# DB25-relay-HV-control.net
KiCad netlist of a schematic drawn in Altium Designer
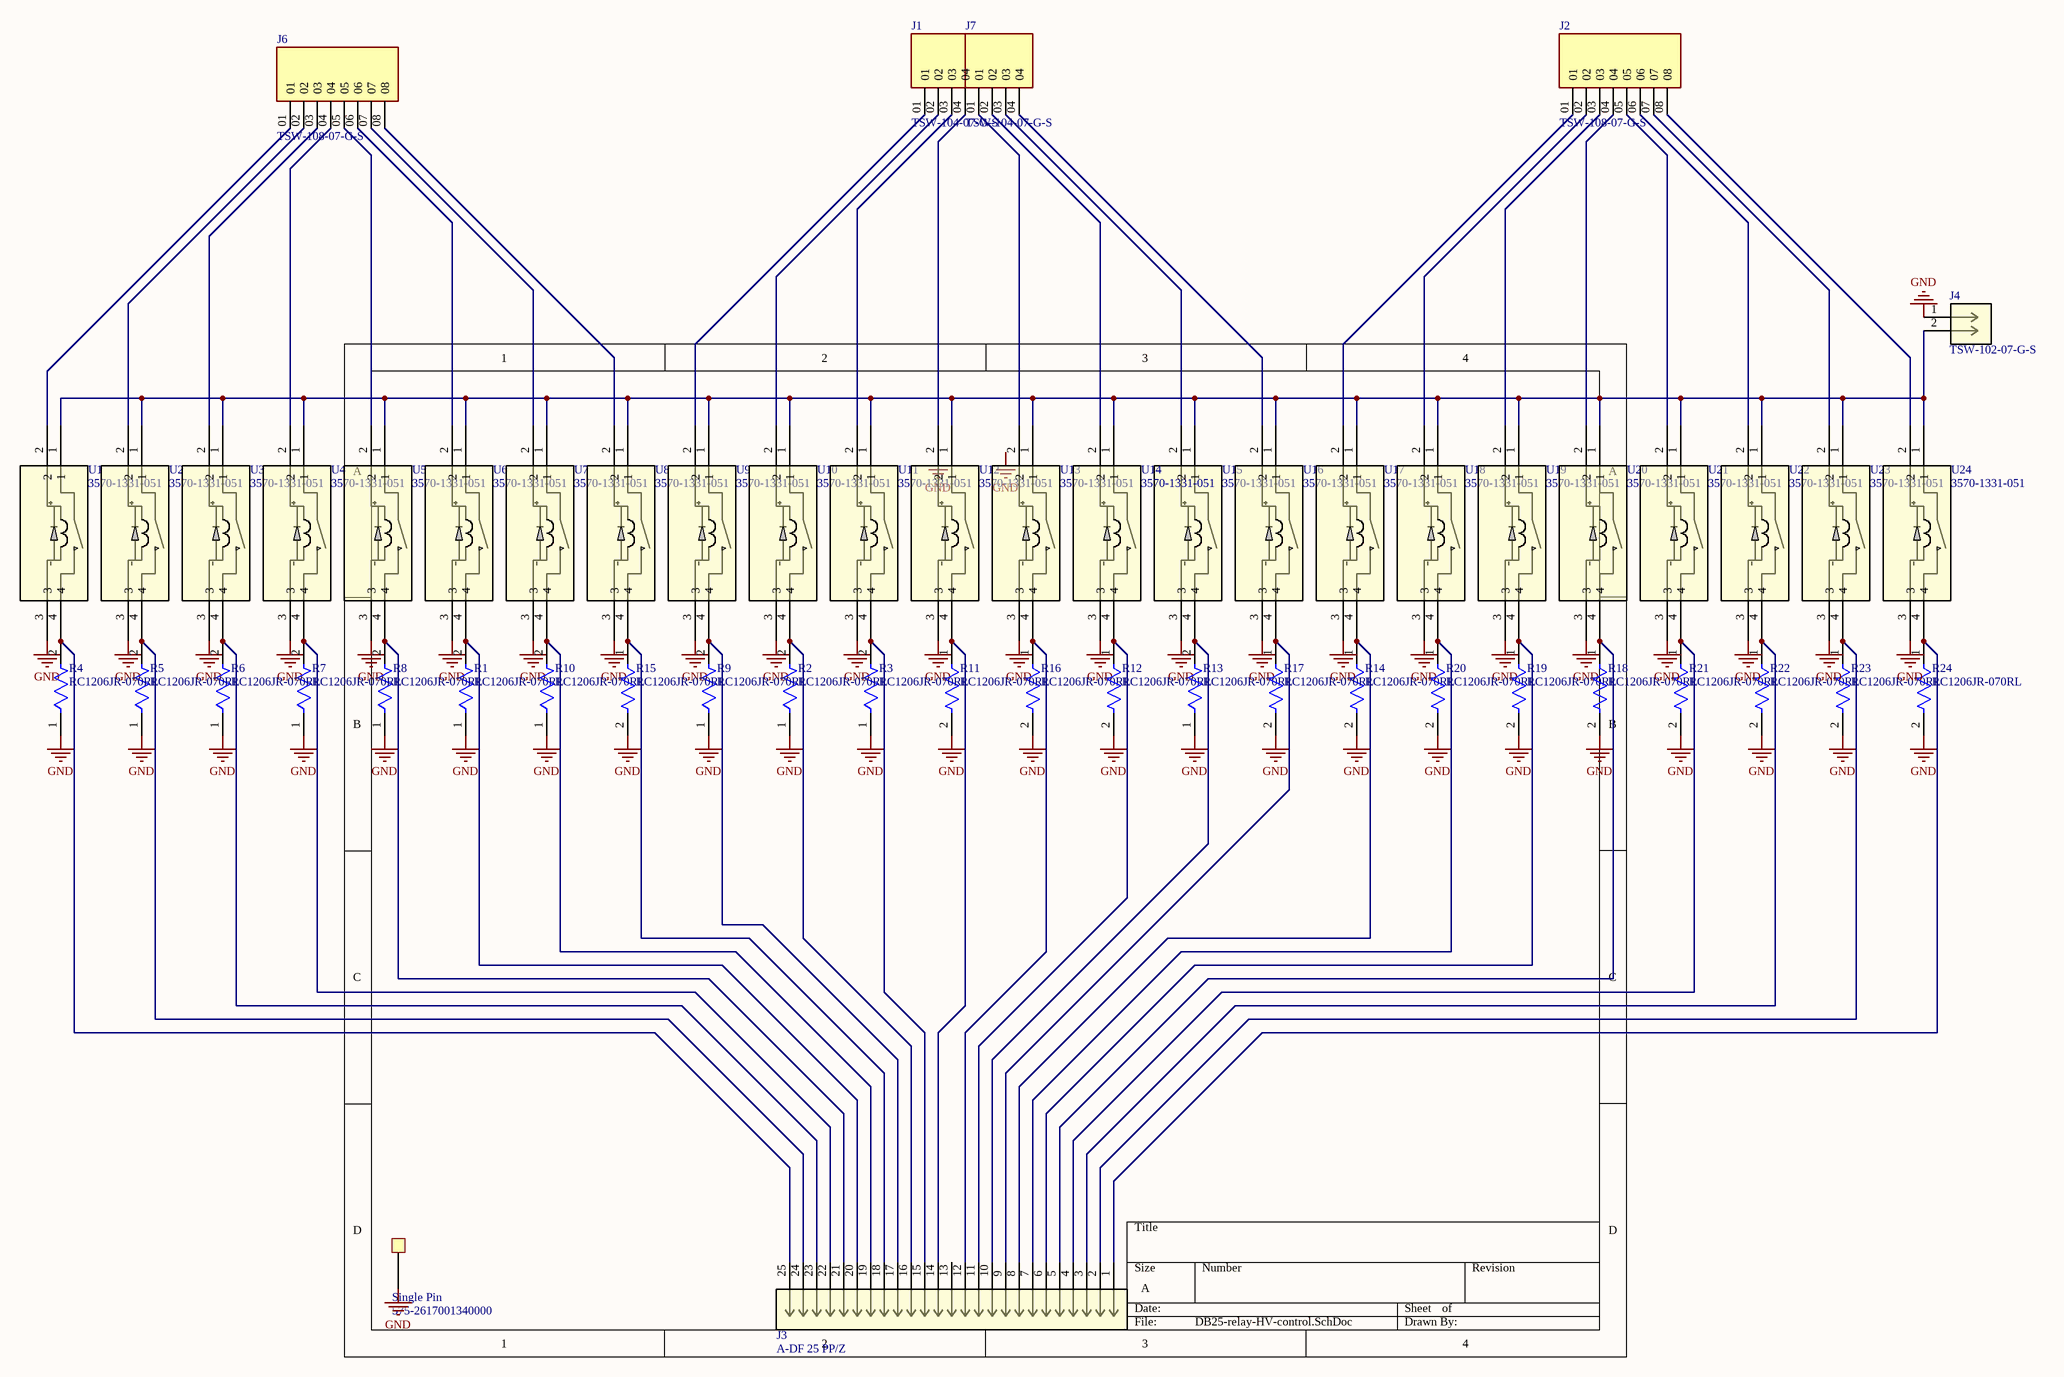
[diagram p0: DB25-relay-HV-control.SchDoc]

(export (version "E")
  (design (tool "Eeschema 10.0.6"))
  (components
    (comp (ref "J1")
      (value "TSW-104-07-G-S")
      (footprint "SAMTEC_TSW-104-07-G-S")
      (fields (field (name "MP") "altium_native_batch"))
      (libsource (lib "SchlibLafe") (part "TSW-104-07-G-S"))
    )
    (comp (ref "J2")
      (value "TSW-108-07-G-S")
      (footprint "SAMTEC_TSW-108-07-G-S")
      (description "TSW - Samtec 2.54mm Pin Header 10.92mm Overall Pin Length (07) - Fast Stock")
      (fields (field (name "MF") "Samtec Inc."))
      (libsource (lib "SchlibLafe") (part "TSW-108-07-G-S"))
    )
    (comp (ref "J3")
      (value "A-DF 25 PP/Z")
      (footprint "CONN_A-DF 25 PPZ_ASM")
      (description "No Description Available")
      (fields (field (name "COPYRIGHT") "Copyright (C) 2024 Ultra Librarian. All rights reserved."))
      (libsource (lib "SchlibLafe") (part "A-DF 25 PPZ"))
    )
    (comp (ref "J4")
      (value "TSW-102-07-G-S")
      (footprint "CON2_1X2_TU_TSW")
      (description "No Description Available")
      (fields (field (name "COPYRIGHT") "Copyright (C) 2024 Ultra Librarian. All rights reserved."))
      (libsource (lib "SchlibLafe") (part "TSW-102-07-G-S"))
    )
    (comp (ref "J5")
      (value "Single Pin")
      (footprint "Single PC Pin")
      (fields (field (name "SUPPLIER PART NUMBER 1") "575-2617001340000"))
      (libsource (lib "SchlibLafe") (part "Single PC Pin"))
    )
    (comp (ref "J6")
      (value "TSW-108-07-G-S")
      (footprint "SAMTEC_TSW-108-07-G-S")
      (description "TSW - Samtec 2.54mm Pin Header 10.92mm Overall Pin Length (07) - Fast Stock")
      (fields (field (name "MF") "Samtec Inc."))
      (libsource (lib "SchlibLafe") (part "TSW-108-07-G-S"))
    )
    (comp (ref "J7")
      (value "TSW-104-07-G-S")
      (footprint "SAMTEC_TSW-104-07-G-S")
      (fields (field (name "MP") "altium_native_batch"))
      (libsource (lib "SchlibLafe") (part "TSW-104-07-G-S"))
    )
    (comp (ref "R1")
      (value "RC1206JR-070RL")
      (footprint "FP-RC1206-MFG")
      (description "RES SMD 0 OHM JUMPER 1/4W 1206")
      (fields
        (field (name "MANUFACTURER") "YAGEO")
        (field (name "OCTOPART") "https://octopart.com/rc1206jr-070rl-yageo-40025601")
      )
      (libsource (lib "Altium Content Vault") (part "1029c3af85768c4190bb7ad29bc67b5"))
    )
    (comp (ref "R2")
      (value "RC1206JR-070RL")
      (footprint "FP-RC1206-MFG")
      (description "RES SMD 0 OHM JUMPER 1/4W 1206")
      (fields
        (field (name "MANUFACTURER") "YAGEO")
        (field (name "OCTOPART") "https://octopart.com/rc1206jr-070rl-yageo-40025601")
      )
      (libsource (lib "Altium Content Vault") (part "1029c3af85768c4190bb7ad29bc67b5"))
    )
    (comp (ref "R3")
      (value "RC1206JR-070RL")
      (footprint "FP-RC1206-MFG")
      (description "RES SMD 0 OHM JUMPER 1/4W 1206")
      (fields
        (field (name "MANUFACTURER") "YAGEO")
        (field (name "OCTOPART") "https://octopart.com/rc1206jr-070rl-yageo-40025601")
      )
      (libsource (lib "Altium Content Vault") (part "1029c3af85768c4190bb7ad29bc67b5"))
    )
    (comp (ref "R4")
      (value "RC1206JR-070RL")
      (footprint "FP-RC1206-MFG")
      (description "RES SMD 0 OHM JUMPER 1/4W 1206")
      (fields
        (field (name "MANUFACTURER") "YAGEO")
        (field (name "OCTOPART") "https://octopart.com/rc1206jr-070rl-yageo-40025601")
      )
      (libsource (lib "Altium Content Vault") (part "1029c3af85768c4190bb7ad29bc67b5"))
    )
    (comp (ref "R5")
      (value "RC1206JR-070RL")
      (footprint "FP-RC1206-MFG")
      (description "RES SMD 0 OHM JUMPER 1/4W 1206")
      (fields
        (field (name "MANUFACTURER") "YAGEO")
        (field (name "OCTOPART") "https://octopart.com/rc1206jr-070rl-yageo-40025601")
      )
      (libsource (lib "Altium Content Vault") (part "1029c3af85768c4190bb7ad29bc67b5"))
    )
    (comp (ref "R6")
      (value "RC1206JR-070RL")
      (footprint "FP-RC1206-MFG")
      (description "RES SMD 0 OHM JUMPER 1/4W 1206")
      (fields
        (field (name "MANUFACTURER") "YAGEO")
        (field (name "OCTOPART") "https://octopart.com/rc1206jr-070rl-yageo-40025601")
      )
      (libsource (lib "Altium Content Vault") (part "1029c3af85768c4190bb7ad29bc67b5"))
    )
    (comp (ref "R7")
      (value "RC1206JR-070RL")
      (footprint "FP-RC1206-MFG")
      (description "RES SMD 0 OHM JUMPER 1/4W 1206")
      (fields
        (field (name "MANUFACTURER") "YAGEO")
        (field (name "OCTOPART") "https://octopart.com/rc1206jr-070rl-yageo-40025601")
      )
      (libsource (lib "Altium Content Vault") (part "1029c3af85768c4190bb7ad29bc67b5"))
    )
    (comp (ref "R8")
      (value "RC1206JR-070RL")
      (footprint "FP-RC1206-MFG")
      (description "RES SMD 0 OHM JUMPER 1/4W 1206")
      (fields
        (field (name "MANUFACTURER") "YAGEO")
        (field (name "OCTOPART") "https://octopart.com/rc1206jr-070rl-yageo-40025601")
      )
      (libsource (lib "Altium Content Vault") (part "1029c3af85768c4190bb7ad29bc67b5"))
    )
    (comp (ref "R9")
      (value "RC1206JR-070RL")
      (footprint "FP-RC1206-MFG")
      (description "RES SMD 0 OHM JUMPER 1/4W 1206")
      (fields
        (field (name "MANUFACTURER") "YAGEO")
        (field (name "OCTOPART") "https://octopart.com/rc1206jr-070rl-yageo-40025601")
      )
      (libsource (lib "Altium Content Vault") (part "1029c3af85768c4190bb7ad29bc67b5"))
    )
    (comp (ref "R10")
      (value "RC1206JR-070RL")
      (footprint "FP-RC1206-MFG")
      (description "RES SMD 0 OHM JUMPER 1/4W 1206")
      (fields
        (field (name "MANUFACTURER") "YAGEO")
        (field (name "OCTOPART") "https://octopart.com/rc1206jr-070rl-yageo-40025601")
      )
      (libsource (lib "Altium Content Vault") (part "1029c3af85768c4190bb7ad29bc67b5"))
    )
    (comp (ref "R11")
      (value "RC1206JR-070RL")
      (footprint "FP-RC1206-MFG")
      (description "RES SMD 0 OHM JUMPER 1/4W 1206")
      (fields
        (field (name "MANUFACTURER") "YAGEO")
        (field (name "OCTOPART") "https://octopart.com/rc1206jr-070rl-yageo-40025601")
      )
      (libsource (lib "Altium Content Vault") (part "1029c3af85768c4190bb7ad29bc67b5"))
    )
    (comp (ref "R12")
      (value "RC1206JR-070RL")
      (footprint "FP-RC1206-MFG")
      (description "RES SMD 0 OHM JUMPER 1/4W 1206")
      (fields
        (field (name "MANUFACTURER") "YAGEO")
        (field (name "OCTOPART") "https://octopart.com/rc1206jr-070rl-yageo-40025601")
      )
      (libsource (lib "Altium Content Vault") (part "1029c3af85768c4190bb7ad29bc67b5"))
    )
    (comp (ref "R13")
      (value "RC1206JR-070RL")
      (footprint "FP-RC1206-MFG")
      (description "RES SMD 0 OHM JUMPER 1/4W 1206")
      (fields
        (field (name "MANUFACTURER") "YAGEO")
        (field (name "OCTOPART") "https://octopart.com/rc1206jr-070rl-yageo-40025601")
      )
      (libsource (lib "Altium Content Vault") (part "1029c3af85768c4190bb7ad29bc67b5"))
    )
    (comp (ref "R14")
      (value "RC1206JR-070RL")
      (footprint "FP-RC1206-MFG")
      (description "RES SMD 0 OHM JUMPER 1/4W 1206")
      (fields
        (field (name "MANUFACTURER") "YAGEO")
        (field (name "OCTOPART") "https://octopart.com/rc1206jr-070rl-yageo-40025601")
      )
      (libsource (lib "Altium Content Vault") (part "1029c3af85768c4190bb7ad29bc67b5"))
    )
    (comp (ref "R15")
      (value "RC1206JR-070RL")
      (footprint "FP-RC1206-MFG")
      (description "RES SMD 0 OHM JUMPER 1/4W 1206")
      (fields
        (field (name "MANUFACTURER") "YAGEO")
        (field (name "OCTOPART") "https://octopart.com/rc1206jr-070rl-yageo-40025601")
      )
      (libsource (lib "Altium Content Vault") (part "1029c3af85768c4190bb7ad29bc67b5"))
    )
    (comp (ref "R16")
      (value "RC1206JR-070RL")
      (footprint "FP-RC1206-MFG")
      (description "RES SMD 0 OHM JUMPER 1/4W 1206")
      (fields
        (field (name "MANUFACTURER") "YAGEO")
        (field (name "OCTOPART") "https://octopart.com/rc1206jr-070rl-yageo-40025601")
      )
      (libsource (lib "Altium Content Vault") (part "1029c3af85768c4190bb7ad29bc67b5"))
    )
    (comp (ref "R17")
      (value "RC1206JR-070RL")
      (footprint "FP-RC1206-MFG")
      (description "RES SMD 0 OHM JUMPER 1/4W 1206")
      (fields
        (field (name "MANUFACTURER") "YAGEO")
        (field (name "OCTOPART") "https://octopart.com/rc1206jr-070rl-yageo-40025601")
      )
      (libsource (lib "Altium Content Vault") (part "1029c3af85768c4190bb7ad29bc67b5"))
    )
    (comp (ref "R18")
      (value "RC1206JR-070RL")
      (footprint "FP-RC1206-MFG")
      (description "RES SMD 0 OHM JUMPER 1/4W 1206")
      (fields
        (field (name "MANUFACTURER") "YAGEO")
        (field (name "OCTOPART") "https://octopart.com/rc1206jr-070rl-yageo-40025601")
      )
      (libsource (lib "Altium Content Vault") (part "1029c3af85768c4190bb7ad29bc67b5"))
    )
    (comp (ref "R19")
      (value "RC1206JR-070RL")
      (footprint "FP-RC1206-MFG")
      (description "RES SMD 0 OHM JUMPER 1/4W 1206")
      (fields
        (field (name "MANUFACTURER") "YAGEO")
        (field (name "OCTOPART") "https://octopart.com/rc1206jr-070rl-yageo-40025601")
      )
      (libsource (lib "Altium Content Vault") (part "1029c3af85768c4190bb7ad29bc67b5"))
    )
    (comp (ref "R20")
      (value "RC1206JR-070RL")
      (footprint "FP-RC1206-MFG")
      (description "RES SMD 0 OHM JUMPER 1/4W 1206")
      (fields
        (field (name "MANUFACTURER") "YAGEO")
        (field (name "OCTOPART") "https://octopart.com/rc1206jr-070rl-yageo-40025601")
      )
      (libsource (lib "Altium Content Vault") (part "1029c3af85768c4190bb7ad29bc67b5"))
    )
    (comp (ref "R21")
      (value "RC1206JR-070RL")
      (footprint "FP-RC1206-MFG")
      (description "RES SMD 0 OHM JUMPER 1/4W 1206")
      (fields
        (field (name "MANUFACTURER") "YAGEO")
        (field (name "OCTOPART") "https://octopart.com/rc1206jr-070rl-yageo-40025601")
      )
      (libsource (lib "Altium Content Vault") (part "1029c3af85768c4190bb7ad29bc67b5"))
    )
    (comp (ref "R22")
      (value "RC1206JR-070RL")
      (footprint "FP-RC1206-MFG")
      (description "RES SMD 0 OHM JUMPER 1/4W 1206")
      (fields
        (field (name "MANUFACTURER") "YAGEO")
        (field (name "OCTOPART") "https://octopart.com/rc1206jr-070rl-yageo-40025601")
      )
      (libsource (lib "Altium Content Vault") (part "1029c3af85768c4190bb7ad29bc67b5"))
    )
    (comp (ref "R23")
      (value "RC1206JR-070RL")
      (footprint "FP-RC1206-MFG")
      (description "RES SMD 0 OHM JUMPER 1/4W 1206")
      (fields
        (field (name "MANUFACTURER") "YAGEO")
        (field (name "OCTOPART") "https://octopart.com/rc1206jr-070rl-yageo-40025601")
      )
      (libsource (lib "Altium Content Vault") (part "1029c3af85768c4190bb7ad29bc67b5"))
    )
    (comp (ref "R24")
      (value "RC1206JR-070RL")
      (footprint "FP-RC1206-MFG")
      (description "RES SMD 0 OHM JUMPER 1/4W 1206")
      (fields
        (field (name "MANUFACTURER") "YAGEO")
        (field (name "OCTOPART") "https://octopart.com/rc1206jr-070rl-yageo-40025601")
      )
      (libsource (lib "Altium Content Vault") (part "1029c3af85768c4190bb7ad29bc67b5"))
    )
    (comp (ref "U1")
      (value "3570-1331-051")
      (footprint "SIP_3570-1331_COM")
      (description "No Description Available")
      (fields (field (name "COPYRIGHT") "Copyright (C) 2024 Ultra Librarian. All rights reserved."))
      (libsource (lib "") (part "3570-1331-051_1"))
    )
    (comp (ref "U2")
      (value "3570-1331-051")
      (footprint "SIP_3570-1331_COM")
      (description "No Description Available")
      (fields (field (name "COPYRIGHT") "Copyright (C) 2024 Ultra Librarian. All rights reserved."))
      (libsource (lib "") (part "3570-1331-051_1"))
    )
    (comp (ref "U3")
      (value "3570-1331-051")
      (footprint "SIP_3570-1331_COM")
      (description "No Description Available")
      (fields (field (name "COPYRIGHT") "Copyright (C) 2024 Ultra Librarian. All rights reserved."))
      (libsource (lib "") (part "3570-1331-051_1"))
    )
    (comp (ref "U4")
      (value "3570-1331-051")
      (footprint "SIP_3570-1331_COM")
      (description "No Description Available")
      (fields (field (name "COPYRIGHT") "Copyright (C) 2024 Ultra Librarian. All rights reserved."))
      (libsource (lib "") (part "3570-1331-051_1"))
    )
    (comp (ref "U5")
      (value "3570-1331-051")
      (footprint "SIP_3570-1331_COM")
      (description "No Description Available")
      (fields (field (name "COPYRIGHT") "Copyright (C) 2024 Ultra Librarian. All rights reserved."))
      (libsource (lib "SchlibAnna") (part "3570-1331-051"))
    )
    (comp (ref "U6")
      (value "3570-1331-051")
      (footprint "SIP_3570-1331_COM")
      (description "No Description Available")
      (fields (field (name "COPYRIGHT") "Copyright (C) 2024 Ultra Librarian. All rights reserved."))
      (libsource (lib "SchlibAnna") (part "3570-1331-051"))
    )
    (comp (ref "U7")
      (value "3570-1331-051")
      (footprint "SIP_3570-1331_COM")
      (description "No Description Available")
      (fields (field (name "COPYRIGHT") "Copyright (C) 2024 Ultra Librarian. All rights reserved."))
      (libsource (lib "SchlibAnna") (part "3570-1331-051"))
    )
    (comp (ref "U8")
      (value "3570-1331-051")
      (footprint "SIP_3570-1331_COM")
      (description "No Description Available")
      (fields (field (name "COPYRIGHT") "Copyright (C) 2024 Ultra Librarian. All rights reserved."))
      (libsource (lib "SchlibAnna") (part "3570-1331-051"))
    )
    (comp (ref "U9")
      (value "3570-1331-051")
      (footprint "SIP_3570-1331_COM")
      (description "No Description Available")
      (fields (field (name "COPYRIGHT") "Copyright (C) 2024 Ultra Librarian. All rights reserved."))
      (libsource (lib "SchlibAnna") (part "3570-1331-051"))
    )
    (comp (ref "U10")
      (value "3570-1331-051")
      (footprint "SIP_3570-1331_COM")
      (description "No Description Available")
      (fields (field (name "COPYRIGHT") "Copyright (C) 2024 Ultra Librarian. All rights reserved."))
      (libsource (lib "SchlibAnna") (part "3570-1331-051"))
    )
    (comp (ref "U11")
      (value "3570-1331-051")
      (footprint "SIP_3570-1331_COM")
      (description "No Description Available")
      (fields (field (name "COPYRIGHT") "Copyright (C) 2024 Ultra Librarian. All rights reserved."))
      (libsource (lib "SchlibAnna") (part "3570-1331-051"))
    )
    (comp (ref "U12")
      (value "3570-1331-051")
      (footprint "SIP_3570-1331_COM")
      (description "No Description Available")
      (fields (field (name "COPYRIGHT") "Copyright (C) 2024 Ultra Librarian. All rights reserved."))
      (libsource (lib "SchlibAnna") (part "3570-1331-051"))
    )
    (comp (ref "U13")
      (value "3570-1331-051")
      (footprint "SIP_3570-1331_COM")
      (description "No Description Available")
      (fields (field (name "COPYRIGHT") "Copyright (C) 2024 Ultra Librarian. All rights reserved."))
      (libsource (lib "SchlibAnna") (part "3570-1331-051"))
    )
    (comp (ref "U14")
      (value "3570-1331-051")
      (footprint "SIP_3570-1331_COM")
      (description "No Description Available")
      (fields (field (name "COPYRIGHT") "Copyright (C) 2024 Ultra Librarian. All rights reserved."))
      (libsource (lib "SchlibAnna") (part "3570-1331-051"))
    )
    (comp (ref "U15")
      (value "3570-1331-051")
      (footprint "SIP_3570-1331_COM")
      (description "No Description Available")
      (fields (field (name "COPYRIGHT") "Copyright (C) 2024 Ultra Librarian. All rights reserved."))
      (libsource (lib "SchlibAnna") (part "3570-1331-051"))
    )
    (comp (ref "U16")
      (value "3570-1331-051")
      (footprint "SIP_3570-1331_COM")
      (description "No Description Available")
      (fields (field (name "COPYRIGHT") "Copyright (C) 2024 Ultra Librarian. All rights reserved."))
      (libsource (lib "SchlibAnna") (part "3570-1331-051"))
    )
    (comp (ref "U17")
      (value "3570-1331-051")
      (footprint "SIP_3570-1331_COM")
      (description "No Description Available")
      (fields (field (name "COPYRIGHT") "Copyright (C) 2024 Ultra Librarian. All rights reserved."))
      (libsource (lib "SchlibAnna") (part "3570-1331-051"))
    )
    (comp (ref "U18")
      (value "3570-1331-051")
      (footprint "SIP_3570-1331_COM")
      (description "No Description Available")
      (fields (field (name "COPYRIGHT") "Copyright (C) 2024 Ultra Librarian. All rights reserved."))
      (libsource (lib "SchlibAnna") (part "3570-1331-051"))
    )
    (comp (ref "U19")
      (value "3570-1331-051")
      (footprint "SIP_3570-1331_COM")
      (description "No Description Available")
      (fields (field (name "COPYRIGHT") "Copyright (C) 2024 Ultra Librarian. All rights reserved."))
      (libsource (lib "SchlibAnna") (part "3570-1331-051"))
    )
    (comp (ref "U20")
      (value "3570-1331-051")
      (footprint "SIP_3570-1331_COM")
      (description "No Description Available")
      (fields (field (name "COPYRIGHT") "Copyright (C) 2024 Ultra Librarian. All rights reserved."))
      (libsource (lib "SchlibAnna") (part "3570-1331-051"))
    )
    (comp (ref "U21")
      (value "3570-1331-051")
      (footprint "SIP_3570-1331_COM")
      (description "No Description Available")
      (fields (field (name "COPYRIGHT") "Copyright (C) 2024 Ultra Librarian. All rights reserved."))
      (libsource (lib "SchlibAnna") (part "3570-1331-051"))
    )
    (comp (ref "U22")
      (value "3570-1331-051")
      (footprint "SIP_3570-1331_COM")
      (description "No Description Available")
      (fields (field (name "COPYRIGHT") "Copyright (C) 2024 Ultra Librarian. All rights reserved."))
      (libsource (lib "SchlibAnna") (part "3570-1331-051"))
    )
    (comp (ref "U23")
      (value "3570-1331-051")
      (footprint "SIP_3570-1331_COM")
      (description "No Description Available")
      (fields (field (name "COPYRIGHT") "Copyright (C) 2024 Ultra Librarian. All rights reserved."))
      (libsource (lib "SchlibAnna") (part "3570-1331-051"))
    )
    (comp (ref "U24")
      (value "3570-1331-051")
      (footprint "SIP_3570-1331_COM")
      (description "No Description Available")
      (fields (field (name "COPYRIGHT") "Copyright (C) 2024 Ultra Librarian. All rights reserved."))
      (libsource (lib "SchlibAnna") (part "3570-1331-051"))
    )
  )
  (nets
    (net (code "1") (name "GND") (class "Default")
      (node (ref "J4") (pin "1") (pinfunction "1_1") (pintype "passive"))
      (node (ref "J5") (pin "1") (pinfunction "1_1") (pintype "passive"))
      (node (ref "R1") (pin "1") (pinfunction "1_1") (pintype "passive"))
      (node (ref "R10") (pin "1") (pinfunction "1_1") (pintype "passive"))
      (node (ref "R11") (pin "2") (pinfunction "2_2") (pintype "passive"))
      (node (ref "R12") (pin "2") (pinfunction "2_2") (pintype "passive"))
      (node (ref "R13") (pin "1") (pinfunction "1_1") (pintype "passive"))
      (node (ref "R14") (pin "2") (pinfunction "2_2") (pintype "passive"))
      (node (ref "R15") (pin "2") (pinfunction "2_2") (pintype "passive"))
      (node (ref "R16") (pin "2") (pinfunction "2_2") (pintype "passive"))
      (node (ref "R17") (pin "2") (pinfunction "2_2") (pintype "passive"))
      (node (ref "R18") (pin "2") (pinfunction "2_2") (pintype "passive"))
      (node (ref "R19") (pin "2") (pinfunction "2_2") (pintype "passive"))
      (node (ref "R2") (pin "1") (pinfunction "1_1") (pintype "passive"))
      (node (ref "R20") (pin "2") (pinfunction "2_2") (pintype "passive"))
      (node (ref "R21") (pin "2") (pinfunction "2_2") (pintype "passive"))
      (node (ref "R22") (pin "2") (pinfunction "2_2") (pintype "passive"))
      (node (ref "R23") (pin "2") (pinfunction "2_2") (pintype "passive"))
      (node (ref "R24") (pin "2") (pinfunction "2_2") (pintype "passive"))
      (node (ref "R3") (pin "1") (pinfunction "1_1") (pintype "passive"))
      (node (ref "R4") (pin "1") (pinfunction "1_1") (pintype "passive"))
      (node (ref "R5") (pin "1") (pinfunction "1_1") (pintype "passive"))
      (node (ref "R6") (pin "1") (pinfunction "1_1") (pintype "passive"))
      (node (ref "R7") (pin "1") (pinfunction "1_1") (pintype "passive"))
      (node (ref "R8") (pin "1") (pinfunction "1_1") (pintype "passive"))
      (node (ref "R9") (pin "1") (pinfunction "1_1") (pintype "passive"))
      (node (ref "U1") (pin "3") (pinfunction "3_3") (pintype "passive"))
      (node (ref "U10") (pin "3") (pinfunction "3_3") (pintype "passive"))
      (node (ref "U11") (pin "3") (pinfunction "3_3") (pintype "passive"))
      (node (ref "U12") (pin "3") (pinfunction "3_3") (pintype "passive"))
      (node (ref "U13") (pin "3") (pinfunction "3_3") (pintype "passive"))
      (node (ref "U14") (pin "3") (pinfunction "3_3") (pintype "passive"))
      (node (ref "U15") (pin "3") (pinfunction "3_3") (pintype "passive"))
      (node (ref "U16") (pin "3") (pinfunction "3_3") (pintype "passive"))
      (node (ref "U17") (pin "3") (pinfunction "3_3") (pintype "passive"))
      (node (ref "U18") (pin "3") (pinfunction "3_3") (pintype "passive"))
      (node (ref "U19") (pin "3") (pinfunction "3_3") (pintype "passive"))
      (node (ref "U2") (pin "3") (pinfunction "3_3") (pintype "passive"))
      (node (ref "U20") (pin "3") (pinfunction "3_3") (pintype "passive"))
      (node (ref "U21") (pin "3") (pinfunction "3_3") (pintype "passive"))
      (node (ref "U22") (pin "3") (pinfunction "3_3") (pintype "passive"))
      (node (ref "U23") (pin "3") (pinfunction "3_3") (pintype "passive"))
      (node (ref "U24") (pin "3") (pinfunction "3_3") (pintype "passive"))
      (node (ref "U3") (pin "3") (pinfunction "3_3") (pintype "passive"))
      (node (ref "U4") (pin "3") (pinfunction "3_3") (pintype "passive"))
      (node (ref "U5") (pin "3") (pinfunction "3_3") (pintype "passive"))
      (node (ref "U6") (pin "3") (pinfunction "3_3") (pintype "passive"))
      (node (ref "U7") (pin "3") (pinfunction "3_3") (pintype "passive"))
      (node (ref "U8") (pin "3") (pinfunction "3_3") (pintype "passive"))
      (node (ref "U9") (pin "3") (pinfunction "3_3") (pintype "passive"))
    )
    (net (code "2") (name "Net-(J1-Pad01)") (class "Default")
      (node (ref "J1") (pin "01") (pinfunction "01_01") (pintype "passive"))
      (node (ref "U9") (pin "2") (pinfunction "2_2") (pintype "passive"))
    )
    (net (code "3") (name "Net-(J1-Pad02)") (class "Default")
      (node (ref "J1") (pin "02") (pinfunction "02_02") (pintype "passive"))
      (node (ref "U10") (pin "2") (pinfunction "2_2") (pintype "passive"))
    )
    (net (code "4") (name "Net-(J1-Pad03)") (class "Default")
      (node (ref "J1") (pin "03") (pinfunction "03_03") (pintype "passive"))
      (node (ref "U11") (pin "2") (pinfunction "2_2") (pintype "passive"))
    )
    (net (code "5") (name "Net-(J1-Pad04)") (class "Default")
      (node (ref "J1") (pin "04") (pinfunction "04_04") (pintype "passive"))
      (node (ref "U12") (pin "2") (pinfunction "2_2") (pintype "passive"))
    )
    (net (code "6") (name "Net-(J2-Pad01)") (class "Default")
      (node (ref "J2") (pin "01") (pinfunction "01_01") (pintype "passive"))
      (node (ref "U17") (pin "2") (pinfunction "2_2") (pintype "passive"))
    )
    (net (code "7") (name "Net-(J2-Pad02)") (class "Default")
      (node (ref "J2") (pin "02") (pinfunction "02_02") (pintype "passive"))
      (node (ref "U18") (pin "2") (pinfunction "2_2") (pintype "passive"))
    )
    (net (code "8") (name "Net-(J2-Pad03)") (class "Default")
      (node (ref "J2") (pin "03") (pinfunction "03_03") (pintype "passive"))
      (node (ref "U19") (pin "2") (pinfunction "2_2") (pintype "passive"))
    )
    (net (code "9") (name "Net-(J2-Pad04)") (class "Default")
      (node (ref "J2") (pin "04") (pinfunction "04_04") (pintype "passive"))
      (node (ref "U20") (pin "2") (pinfunction "2_2") (pintype "passive"))
    )
    (net (code "10") (name "Net-(J2-Pad05)") (class "Default")
      (node (ref "J2") (pin "05") (pinfunction "05_05") (pintype "passive"))
      (node (ref "U21") (pin "2") (pinfunction "2_2") (pintype "passive"))
    )
    (net (code "11") (name "Net-(J2-Pad06)") (class "Default")
      (node (ref "J2") (pin "06") (pinfunction "06_06") (pintype "passive"))
      (node (ref "U22") (pin "2") (pinfunction "2_2") (pintype "passive"))
    )
    (net (code "12") (name "Net-(J2-Pad07)") (class "Default")
      (node (ref "J2") (pin "07") (pinfunction "07_07") (pintype "passive"))
      (node (ref "U23") (pin "2") (pinfunction "2_2") (pintype "passive"))
    )
    (net (code "13") (name "Net-(J2-Pad08)") (class "Default")
      (node (ref "J2") (pin "08") (pinfunction "08_08") (pintype "passive"))
      (node (ref "U24") (pin "2") (pinfunction "2_2") (pintype "passive"))
    )
    (net (code "14") (name "Net-(J3-Pad1)") (class "Default")
      (node (ref "J3") (pin "1") (pinfunction "1_1") (pintype "passive"))
      (node (ref "R24") (pin "1") (pinfunction "1_1") (pintype "passive"))
      (node (ref "U24") (pin "4") (pinfunction "4_4") (pintype "passive"))
    )
    (net (code "15") (name "Net-(J3-Pad2)") (class "Default")
      (node (ref "J3") (pin "2") (pinfunction "2_2") (pintype "passive"))
      (node (ref "R23") (pin "1") (pinfunction "1_1") (pintype "passive"))
      (node (ref "U23") (pin "4") (pinfunction "4_4") (pintype "passive"))
    )
    (net (code "16") (name "Net-(J3-Pad3)") (class "Default")
      (node (ref "J3") (pin "3") (pinfunction "3_3") (pintype "passive"))
      (node (ref "R22") (pin "1") (pinfunction "1_1") (pintype "passive"))
      (node (ref "U22") (pin "4") (pinfunction "4_4") (pintype "passive"))
    )
    (net (code "17") (name "Net-(J3-Pad4)") (class "Default")
      (node (ref "J3") (pin "4") (pinfunction "4_4") (pintype "passive"))
      (node (ref "R21") (pin "1") (pinfunction "1_1") (pintype "passive"))
      (node (ref "U21") (pin "4") (pinfunction "4_4") (pintype "passive"))
    )
    (net (code "18") (name "Net-(J3-Pad5)") (class "Default")
      (node (ref "J3") (pin "5") (pinfunction "5_5") (pintype "passive"))
      (node (ref "R18") (pin "1") (pinfunction "1_1") (pintype "passive"))
      (node (ref "U20") (pin "4") (pinfunction "4_4") (pintype "passive"))
    )
    (net (code "19") (name "Net-(J3-Pad6)") (class "Default")
      (node (ref "J3") (pin "6") (pinfunction "6_6") (pintype "passive"))
      (node (ref "R19") (pin "1") (pinfunction "1_1") (pintype "passive"))
      (node (ref "U19") (pin "4") (pinfunction "4_4") (pintype "passive"))
    )
    (net (code "20") (name "Net-(J3-Pad7)") (class "Default")
      (node (ref "J3") (pin "7") (pinfunction "7_7") (pintype "passive"))
      (node (ref "R20") (pin "1") (pinfunction "1_1") (pintype "passive"))
      (node (ref "U18") (pin "4") (pinfunction "4_4") (pintype "passive"))
    )
    (net (code "21") (name "Net-(J3-Pad8)") (class "Default")
      (node (ref "J3") (pin "8") (pinfunction "8_8") (pintype "passive"))
      (node (ref "R14") (pin "1") (pinfunction "1_1") (pintype "passive"))
      (node (ref "U17") (pin "4") (pinfunction "4_4") (pintype "passive"))
    )
    (net (code "22") (name "Net-(J3-Pad9)") (class "Default")
      (node (ref "J3") (pin "9") (pinfunction "9_9") (pintype "passive"))
      (node (ref "R17") (pin "1") (pinfunction "1_1") (pintype "passive"))
      (node (ref "U16") (pin "4") (pinfunction "4_4") (pintype "passive"))
    )
    (net (code "23") (name "Net-(J3-Pad10)") (class "Default")
      (node (ref "J3") (pin "10") (pinfunction "10_10") (pintype "passive"))
      (node (ref "R13") (pin "2") (pinfunction "2_2") (pintype "passive"))
      (node (ref "U15") (pin "4") (pinfunction "4_4") (pintype "passive"))
    )
    (net (code "24") (name "Net-(J3-Pad11)") (class "Default")
      (node (ref "J3") (pin "11") (pinfunction "11_11") (pintype "passive"))
      (node (ref "R12") (pin "1") (pinfunction "1_1") (pintype "passive"))
      (node (ref "U14") (pin "4") (pinfunction "4_4") (pintype "passive"))
    )
    (net (code "25") (name "Net-(J3-Pad12)") (class "Default")
      (node (ref "J3") (pin "12") (pinfunction "12_12") (pintype "passive"))
      (node (ref "R16") (pin "1") (pinfunction "1_1") (pintype "passive"))
      (node (ref "U13") (pin "4") (pinfunction "4_4") (pintype "passive"))
    )
    (net (code "26") (name "Net-(J3-Pad14)") (class "Default")
      (node (ref "J3") (pin "14") (pinfunction "14_14") (pintype "passive"))
      (node (ref "R11") (pin "1") (pinfunction "1_1") (pintype "passive"))
      (node (ref "U12") (pin "4") (pinfunction "4_4") (pintype "passive"))
    )
    (net (code "27") (name "Net-(J3-Pad15)") (class "Default")
      (node (ref "J3") (pin "15") (pinfunction "15_15") (pintype "passive"))
      (node (ref "R3") (pin "2") (pinfunction "2_2") (pintype "passive"))
      (node (ref "U11") (pin "4") (pinfunction "4_4") (pintype "passive"))
    )
    (net (code "28") (name "Net-(J3-Pad16)") (class "Default")
      (node (ref "J3") (pin "16") (pinfunction "16_16") (pintype "passive"))
      (node (ref "R2") (pin "2") (pinfunction "2_2") (pintype "passive"))
      (node (ref "U10") (pin "4") (pinfunction "4_4") (pintype "passive"))
    )
    (net (code "29") (name "Net-(J3-Pad17)") (class "Default")
      (node (ref "J3") (pin "17") (pinfunction "17_17") (pintype "passive"))
      (node (ref "R9") (pin "2") (pinfunction "2_2") (pintype "passive"))
      (node (ref "U9") (pin "4") (pinfunction "4_4") (pintype "passive"))
    )
    (net (code "30") (name "Net-(J3-Pad18)") (class "Default")
      (node (ref "J3") (pin "18") (pinfunction "18_18") (pintype "passive"))
      (node (ref "R15") (pin "1") (pinfunction "1_1") (pintype "passive"))
      (node (ref "U8") (pin "4") (pinfunction "4_4") (pintype "passive"))
    )
    (net (code "31") (name "Net-(J3-Pad19)") (class "Default")
      (node (ref "J3") (pin "19") (pinfunction "19_19") (pintype "passive"))
      (node (ref "R10") (pin "2") (pinfunction "2_2") (pintype "passive"))
      (node (ref "U7") (pin "4") (pinfunction "4_4") (pintype "passive"))
    )
    (net (code "32") (name "Net-(J3-Pad20)") (class "Default")
      (node (ref "J3") (pin "20") (pinfunction "20_20") (pintype "passive"))
      (node (ref "R1") (pin "2") (pinfunction "2_2") (pintype "passive"))
      (node (ref "U6") (pin "4") (pinfunction "4_4") (pintype "passive"))
    )
    (net (code "33") (name "Net-(J3-Pad21)") (class "Default")
      (node (ref "J3") (pin "21") (pinfunction "21_21") (pintype "passive"))
      (node (ref "R8") (pin "2") (pinfunction "2_2") (pintype "passive"))
      (node (ref "U5") (pin "4") (pinfunction "4_4") (pintype "passive"))
    )
    (net (code "34") (name "Net-(J3-Pad22)") (class "Default")
      (node (ref "J3") (pin "22") (pinfunction "22_22") (pintype "passive"))
      (node (ref "R7") (pin "2") (pinfunction "2_2") (pintype "passive"))
      (node (ref "U4") (pin "4") (pinfunction "4_4") (pintype "passive"))
    )
    (net (code "35") (name "Net-(J3-Pad23)") (class "Default")
      (node (ref "J3") (pin "23") (pinfunction "23_23") (pintype "passive"))
      (node (ref "R6") (pin "2") (pinfunction "2_2") (pintype "passive"))
      (node (ref "U3") (pin "4") (pinfunction "4_4") (pintype "passive"))
    )
    (net (code "36") (name "Net-(J3-Pad24)") (class "Default")
      (node (ref "J3") (pin "24") (pinfunction "24_24") (pintype "passive"))
      (node (ref "R5") (pin "2") (pinfunction "2_2") (pintype "passive"))
      (node (ref "U2") (pin "4") (pinfunction "4_4") (pintype "passive"))
    )
    (net (code "37") (name "Net-(J3-Pad25)") (class "Default")
      (node (ref "J3") (pin "25") (pinfunction "25_25") (pintype "passive"))
      (node (ref "R4") (pin "2") (pinfunction "2_2") (pintype "passive"))
      (node (ref "U1") (pin "4") (pinfunction "4_4") (pintype "passive"))
    )
    (net (code "38") (name "Net-(J4-Pad2)") (class "Default")
      (node (ref "J4") (pin "2") (pinfunction "2_2") (pintype "passive"))
      (node (ref "U1") (pin "1") (pinfunction "1_1") (pintype "passive"))
      (node (ref "U10") (pin "1") (pinfunction "1_1") (pintype "passive"))
      (node (ref "U11") (pin "1") (pinfunction "1_1") (pintype "passive"))
      (node (ref "U12") (pin "1") (pinfunction "1_1") (pintype "passive"))
      (node (ref "U13") (pin "1") (pinfunction "1_1") (pintype "passive"))
      (node (ref "U14") (pin "1") (pinfunction "1_1") (pintype "passive"))
      (node (ref "U15") (pin "1") (pinfunction "1_1") (pintype "passive"))
      (node (ref "U16") (pin "1") (pinfunction "1_1") (pintype "passive"))
      (node (ref "U17") (pin "1") (pinfunction "1_1") (pintype "passive"))
      (node (ref "U18") (pin "1") (pinfunction "1_1") (pintype "passive"))
      (node (ref "U19") (pin "1") (pinfunction "1_1") (pintype "passive"))
      (node (ref "U2") (pin "1") (pinfunction "1_1") (pintype "passive"))
      (node (ref "U20") (pin "1") (pinfunction "1_1") (pintype "passive"))
      (node (ref "U21") (pin "1") (pinfunction "1_1") (pintype "passive"))
      (node (ref "U22") (pin "1") (pinfunction "1_1") (pintype "passive"))
      (node (ref "U23") (pin "1") (pinfunction "1_1") (pintype "passive"))
      (node (ref "U24") (pin "1") (pinfunction "1_1") (pintype "passive"))
      (node (ref "U3") (pin "1") (pinfunction "1_1") (pintype "passive"))
      (node (ref "U4") (pin "1") (pinfunction "1_1") (pintype "passive"))
      (node (ref "U5") (pin "1") (pinfunction "1_1") (pintype "passive"))
      (node (ref "U6") (pin "1") (pinfunction "1_1") (pintype "passive"))
      (node (ref "U7") (pin "1") (pinfunction "1_1") (pintype "passive"))
      (node (ref "U8") (pin "1") (pinfunction "1_1") (pintype "passive"))
      (node (ref "U9") (pin "1") (pinfunction "1_1") (pintype "passive"))
    )
    (net (code "39") (name "Net-(J6-Pad01)") (class "Default")
      (node (ref "J6") (pin "01") (pinfunction "01_01") (pintype "passive"))
      (node (ref "U1") (pin "2") (pinfunction "2_2") (pintype "passive"))
    )
    (net (code "40") (name "Net-(J6-Pad02)") (class "Default")
      (node (ref "J6") (pin "02") (pinfunction "02_02") (pintype "passive"))
      (node (ref "U2") (pin "2") (pinfunction "2_2") (pintype "passive"))
    )
    (net (code "41") (name "Net-(J6-Pad03)") (class "Default")
      (node (ref "J6") (pin "03") (pinfunction "03_03") (pintype "passive"))
      (node (ref "U3") (pin "2") (pinfunction "2_2") (pintype "passive"))
    )
    (net (code "42") (name "Net-(J6-Pad04)") (class "Default")
      (node (ref "J6") (pin "04") (pinfunction "04_04") (pintype "passive"))
      (node (ref "U4") (pin "2") (pinfunction "2_2") (pintype "passive"))
    )
    (net (code "43") (name "Net-(J6-Pad05)") (class "Default")
      (node (ref "J6") (pin "05") (pinfunction "05_05") (pintype "passive"))
      (node (ref "U5") (pin "2") (pinfunction "2_2") (pintype "passive"))
    )
    (net (code "44") (name "Net-(J6-Pad06)") (class "Default")
      (node (ref "J6") (pin "06") (pinfunction "06_06") (pintype "passive"))
      (node (ref "U6") (pin "2") (pinfunction "2_2") (pintype "passive"))
    )
    (net (code "45") (name "Net-(J6-Pad07)") (class "Default")
      (node (ref "J6") (pin "07") (pinfunction "07_07") (pintype "passive"))
      (node (ref "U7") (pin "2") (pinfunction "2_2") (pintype "passive"))
    )
    (net (code "46") (name "Net-(J6-Pad08)") (class "Default")
      (node (ref "J6") (pin "08") (pinfunction "08_08") (pintype "passive"))
      (node (ref "U8") (pin "2") (pinfunction "2_2") (pintype "passive"))
    )
    (net (code "47") (name "Net-(J7-Pad01)") (class "Default")
      (node (ref "J7") (pin "01") (pinfunction "01_01") (pintype "passive"))
      (node (ref "U13") (pin "2") (pinfunction "2_2") (pintype "passive"))
    )
    (net (code "48") (name "Net-(J7-Pad02)") (class "Default")
      (node (ref "J7") (pin "02") (pinfunction "02_02") (pintype "passive"))
      (node (ref "U14") (pin "2") (pinfunction "2_2") (pintype "passive"))
    )
    (net (code "49") (name "Net-(J7-Pad03)") (class "Default")
      (node (ref "J7") (pin "03") (pinfunction "03_03") (pintype "passive"))
      (node (ref "U15") (pin "2") (pinfunction "2_2") (pintype "passive"))
    )
    (net (code "50") (name "Net-(J7-Pad04)") (class "Default")
      (node (ref "J7") (pin "04") (pinfunction "04_04") (pintype "passive"))
      (node (ref "U16") (pin "2") (pinfunction "2_2") (pintype "passive"))
    )
    (net (code "51") (name "unconnected-(J3-Pad13)") (class "Default")
      (node (ref "J3") (pin "13") (pinfunction "13_13") (pintype "passive"))
    )
  )
)
